# PIC16F_Schematic.net
KiCad netlist of a schematic drawn in Altium Designer
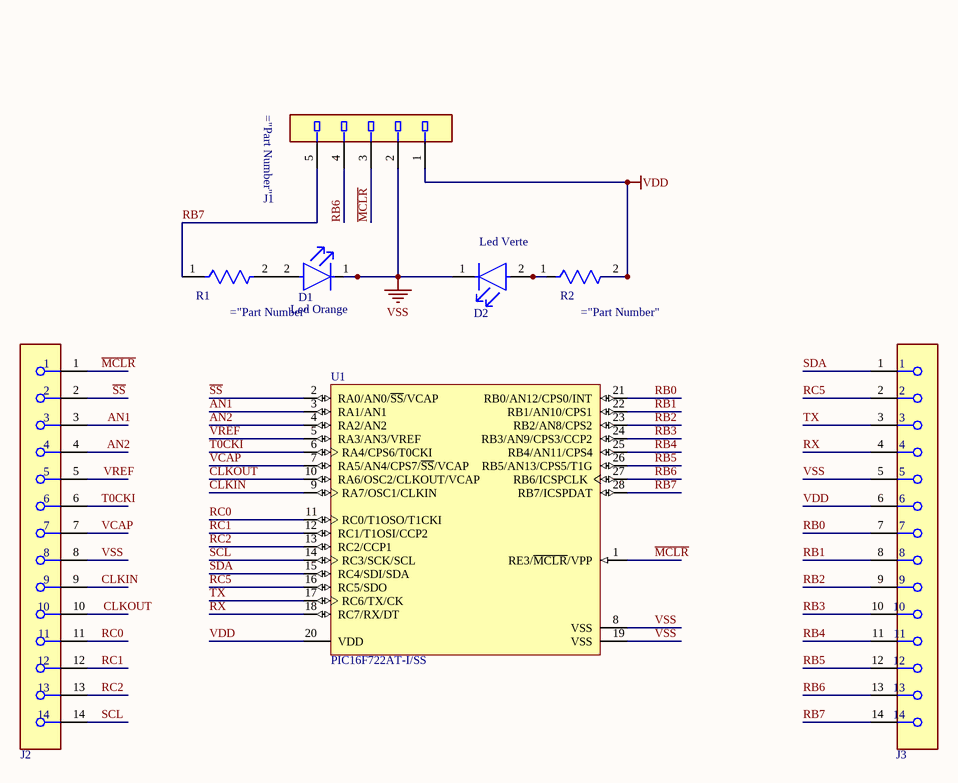
[diagram p0: PIC16F_Schematic.SchDoc]

(export (version "E")
  (design (tool "Eeschema 10.0.6"))
  (components
    (comp (ref "D1")
      (value "LO_Q976-PS-25-0-20-R18")
      (footprint "Osram_Opto_LO_Q976_MFG")
      (libsource (lib "Diode_Osram_Opto_LO_Q976-PS-25-0-20-R18_eec") (part "LO_Q976-PS-25-0-20-R18"))
    )
    (comp (ref "D2")
      (value "LTST-C190GKT")
      (footprint "Lite-On_0_MFG")
      (libsource (lib "Diode_Lite-On_LTST-C190GKT_eec") (part "LTST-C190GKT"))
    )
    (comp (ref "J1")
      (value "61300511121")
      (footprint "Wurth_61300511121_0")
      (libsource (lib "Conn_Wurth_61300511121_eec") (part "61300511121"))
    )
    (comp (ref "J2")
      (value "PPTC141LFBN-RC")
      (footprint "Sullins_0_MFG")
      (libsource (lib "Conn_Sullins_PPTC141LFBN-RC_eec") (part "PPTC141LFBN-RC"))
    )
    (comp (ref "J3")
      (value "PPTC141LFBN-RC")
      (footprint "Sullins_0_MFG")
      (libsource (lib "") (part "PPTC141LFBN-RC_1"))
    )
    (comp (ref "R1")
      (value "RMCF0603FT220R")
      (footprint "Yageo_RC0805_IPC_B")
      (libsource (lib "Res_Stackpole_RMCF0603FT220R_eec") (part "RMCF0603FT220R"))
    )
    (comp (ref "R2")
      (value "RMCF0603FT220R")
      (footprint "Yageo_RC0805_MFG")
      (libsource (lib "Res_Stackpole_RMCF0603FT220R_eec") (part "RMCF0603FT220R"))
    )
    (comp (ref "U1")
      (value "PIC16F722AT-I/SS")
      (footprint "MCHP-SSOP-SS28_M")
      (fields (field (name "MANUFACTURER") "Microchip"))
      (libsource (lib "Microchip_PIC16F722AT_I_SS") (part "PIC16F722AT-I/SS"))
    )
  )
  (nets
    (net (code "1") (name "/AN1") (class "Default")
      (node (ref "J2") (pin "3") (pinfunction "3_3") (pintype "passive"))
      (node (ref "U1") (pin "3") (pinfunction "RA1/AN1_3") (pintype "bidirectional"))
    )
    (net (code "2") (name "/AN2") (class "Default")
      (node (ref "J2") (pin "4") (pinfunction "4_4") (pintype "passive"))
      (node (ref "U1") (pin "4") (pinfunction "RA2/AN2_4") (pintype "bidirectional"))
    )
    (net (code "3") (name "/CLKIN") (class "Default")
      (node (ref "J2") (pin "9") (pinfunction "9_9") (pintype "passive"))
      (node (ref "U1") (pin "9") (pinfunction "RA7/OSC1/CLKIN_9") (pintype "bidirectional"))
    )
    (net (code "4") (name "/CLKOUT") (class "Default")
      (node (ref "J2") (pin "10") (pinfunction "10_10") (pintype "passive"))
      (node (ref "U1") (pin "10") (pinfunction "RA6/OSC2/CLKOUT/VCAP_10") (pintype "bidirectional"))
    )
    (net (code "5") (name "/MCLR") (class "Default")
      (node (ref "J1") (pin "3") (pinfunction "3_3") (pintype "passive"))
      (node (ref "J2") (pin "1") (pinfunction "1_1") (pintype "passive"))
      (node (ref "U1") (pin "1") (pinfunction "RE3/~{MCLR}/VPP_1") (pintype "input"))
    )
    (net (code "6") (name "/RB0") (class "Default")
      (node (ref "J3") (pin "7") (pinfunction "7_7") (pintype "passive"))
      (node (ref "U1") (pin "21") (pinfunction "RB0/AN12/CPS0/INT_21") (pintype "bidirectional"))
    )
    (net (code "7") (name "/RB1") (class "Default")
      (node (ref "J3") (pin "8") (pinfunction "8_8") (pintype "passive"))
      (node (ref "U1") (pin "22") (pinfunction "RB1/AN10/CPS1_22") (pintype "bidirectional"))
    )
    (net (code "8") (name "/RB2") (class "Default")
      (node (ref "J3") (pin "9") (pinfunction "9_9") (pintype "passive"))
      (node (ref "U1") (pin "23") (pinfunction "RB2/AN8/CPS2_23") (pintype "bidirectional"))
    )
    (net (code "9") (name "/RB3") (class "Default")
      (node (ref "J3") (pin "10") (pinfunction "10_10") (pintype "passive"))
      (node (ref "U1") (pin "24") (pinfunction "RB3/AN9/CPS3/CCP2_24") (pintype "bidirectional"))
    )
    (net (code "10") (name "/RB4") (class "Default")
      (node (ref "J3") (pin "11") (pinfunction "11_11") (pintype "passive"))
      (node (ref "U1") (pin "25") (pinfunction "RB4/AN11/CPS4_25") (pintype "bidirectional"))
    )
    (net (code "11") (name "/RB5") (class "Default")
      (node (ref "J3") (pin "12") (pinfunction "12_12") (pintype "passive"))
      (node (ref "U1") (pin "26") (pinfunction "RB5/AN13/CPS5/T1G_26") (pintype "bidirectional"))
    )
    (net (code "12") (name "/RB6") (class "Default")
      (node (ref "J1") (pin "4") (pinfunction "4_4") (pintype "passive"))
      (node (ref "J3") (pin "13") (pinfunction "13_13") (pintype "passive"))
      (node (ref "U1") (pin "27") (pinfunction "RB6/ICSPCLK_27") (pintype "bidirectional"))
    )
    (net (code "13") (name "/RB7") (class "Default")
      (node (ref "J1") (pin "5") (pinfunction "5_5") (pintype "passive"))
      (node (ref "J3") (pin "14") (pinfunction "14_14") (pintype "passive"))
      (node (ref "R1") (pin "1") (pinfunction "1_1") (pintype "passive"))
      (node (ref "U1") (pin "28") (pinfunction "RB7/ICSPDAT_28") (pintype "bidirectional"))
    )
    (net (code "14") (name "/RC0") (class "Default")
      (node (ref "J2") (pin "11") (pinfunction "11_11") (pintype "passive"))
      (node (ref "U1") (pin "11") (pinfunction "RC0/T1OSO/T1CKI_11") (pintype "bidirectional"))
    )
    (net (code "15") (name "/RC1") (class "Default")
      (node (ref "J2") (pin "12") (pinfunction "12_12") (pintype "passive"))
      (node (ref "U1") (pin "12") (pinfunction "RC1/T1OSI/CCP2_12") (pintype "bidirectional"))
    )
    (net (code "16") (name "/RC2") (class "Default")
      (node (ref "J2") (pin "13") (pinfunction "13_13") (pintype "passive"))
      (node (ref "U1") (pin "13") (pinfunction "RC2/CCP1_13") (pintype "bidirectional"))
    )
    (net (code "17") (name "/RC5") (class "Default")
      (node (ref "J3") (pin "2") (pinfunction "2_2") (pintype "passive"))
      (node (ref "U1") (pin "16") (pinfunction "RC5/SDO_16") (pintype "bidirectional"))
    )
    (net (code "18") (name "/RX") (class "Default")
      (node (ref "J3") (pin "4") (pinfunction "4_4") (pintype "passive"))
      (node (ref "U1") (pin "18") (pinfunction "RC7/RX/DT_18") (pintype "bidirectional"))
    )
    (net (code "19") (name "/SCL") (class "Default")
      (node (ref "J2") (pin "14") (pinfunction "14_14") (pintype "passive"))
      (node (ref "U1") (pin "14") (pinfunction "RC3/SCK/SCL_14") (pintype "bidirectional"))
    )
    (net (code "20") (name "/SDA") (class "Default")
      (node (ref "J3") (pin "1") (pinfunction "1_1") (pintype "passive"))
      (node (ref "U1") (pin "15") (pinfunction "RC4/SDI/SDA_15") (pintype "bidirectional"))
    )
    (net (code "21") (name "/SS") (class "Default")
      (node (ref "J2") (pin "2") (pinfunction "2_2") (pintype "passive"))
      (node (ref "U1") (pin "2") (pinfunction "RA0/AN0/~{SS}/VCAP_2") (pintype "bidirectional"))
    )
    (net (code "22") (name "/T0CKI") (class "Default")
      (node (ref "J2") (pin "6") (pinfunction "6_6") (pintype "passive"))
      (node (ref "U1") (pin "6") (pinfunction "RA4/CPS6/T0CKI_6") (pintype "bidirectional"))
    )
    (net (code "23") (name "/TX") (class "Default")
      (node (ref "J3") (pin "3") (pinfunction "3_3") (pintype "passive"))
      (node (ref "U1") (pin "17") (pinfunction "RC6/TX/CK_17") (pintype "bidirectional"))
    )
    (net (code "24") (name "/VCAP") (class "Default")
      (node (ref "J2") (pin "7") (pinfunction "7_7") (pintype "passive"))
      (node (ref "U1") (pin "7") (pinfunction "RA5/AN4/CPS7/~{SS}/VCAP_7") (pintype "bidirectional"))
    )
    (net (code "25") (name "/VREF") (class "Default")
      (node (ref "J2") (pin "5") (pinfunction "5_5") (pintype "passive"))
      (node (ref "U1") (pin "5") (pinfunction "RA3/AN3/VREF_5") (pintype "bidirectional"))
    )
    (net (code "26") (name "Net-(D1-A)") (class "Default")
      (node (ref "D1") (pin "2") (pinfunction "A_2") (pintype "passive"))
      (node (ref "R1") (pin "2") (pinfunction "2_2") (pintype "passive"))
    )
    (net (code "27") (name "Net-(D2-A)") (class "Default")
      (node (ref "D2") (pin "2") (pinfunction "A_2") (pintype "passive"))
      (node (ref "R2") (pin "1") (pinfunction "1_1") (pintype "passive"))
    )
    (net (code "28") (name "VDD") (class "Default")
      (node (ref "J1") (pin "1") (pinfunction "1_1") (pintype "passive"))
      (node (ref "J3") (pin "6") (pinfunction "6_6") (pintype "passive"))
      (node (ref "R2") (pin "2") (pinfunction "2_2") (pintype "passive"))
      (node (ref "U1") (pin "20") (pinfunction "VDD_20") (pintype "power_in"))
    )
    (net (code "29") (name "VSS") (class "Default")
      (node (ref "D1") (pin "1") (pinfunction "C_1") (pintype "passive"))
      (node (ref "D2") (pin "1") (pinfunction "C_1") (pintype "passive"))
      (node (ref "J1") (pin "2") (pinfunction "2_2") (pintype "passive"))
      (node (ref "J2") (pin "8") (pinfunction "8_8") (pintype "passive"))
      (node (ref "J3") (pin "5") (pinfunction "5_5") (pintype "passive"))
      (node (ref "U1") (pin "19") (pinfunction "VSS_19") (pintype "power_in"))
      (node (ref "U1") (pin "8") (pinfunction "VSS_8") (pintype "power_in"))
    )
  )
)
